# SCH_Keyboard_2024-07-21.net
KiCad netlist of a schematic drawn in EasyEDA
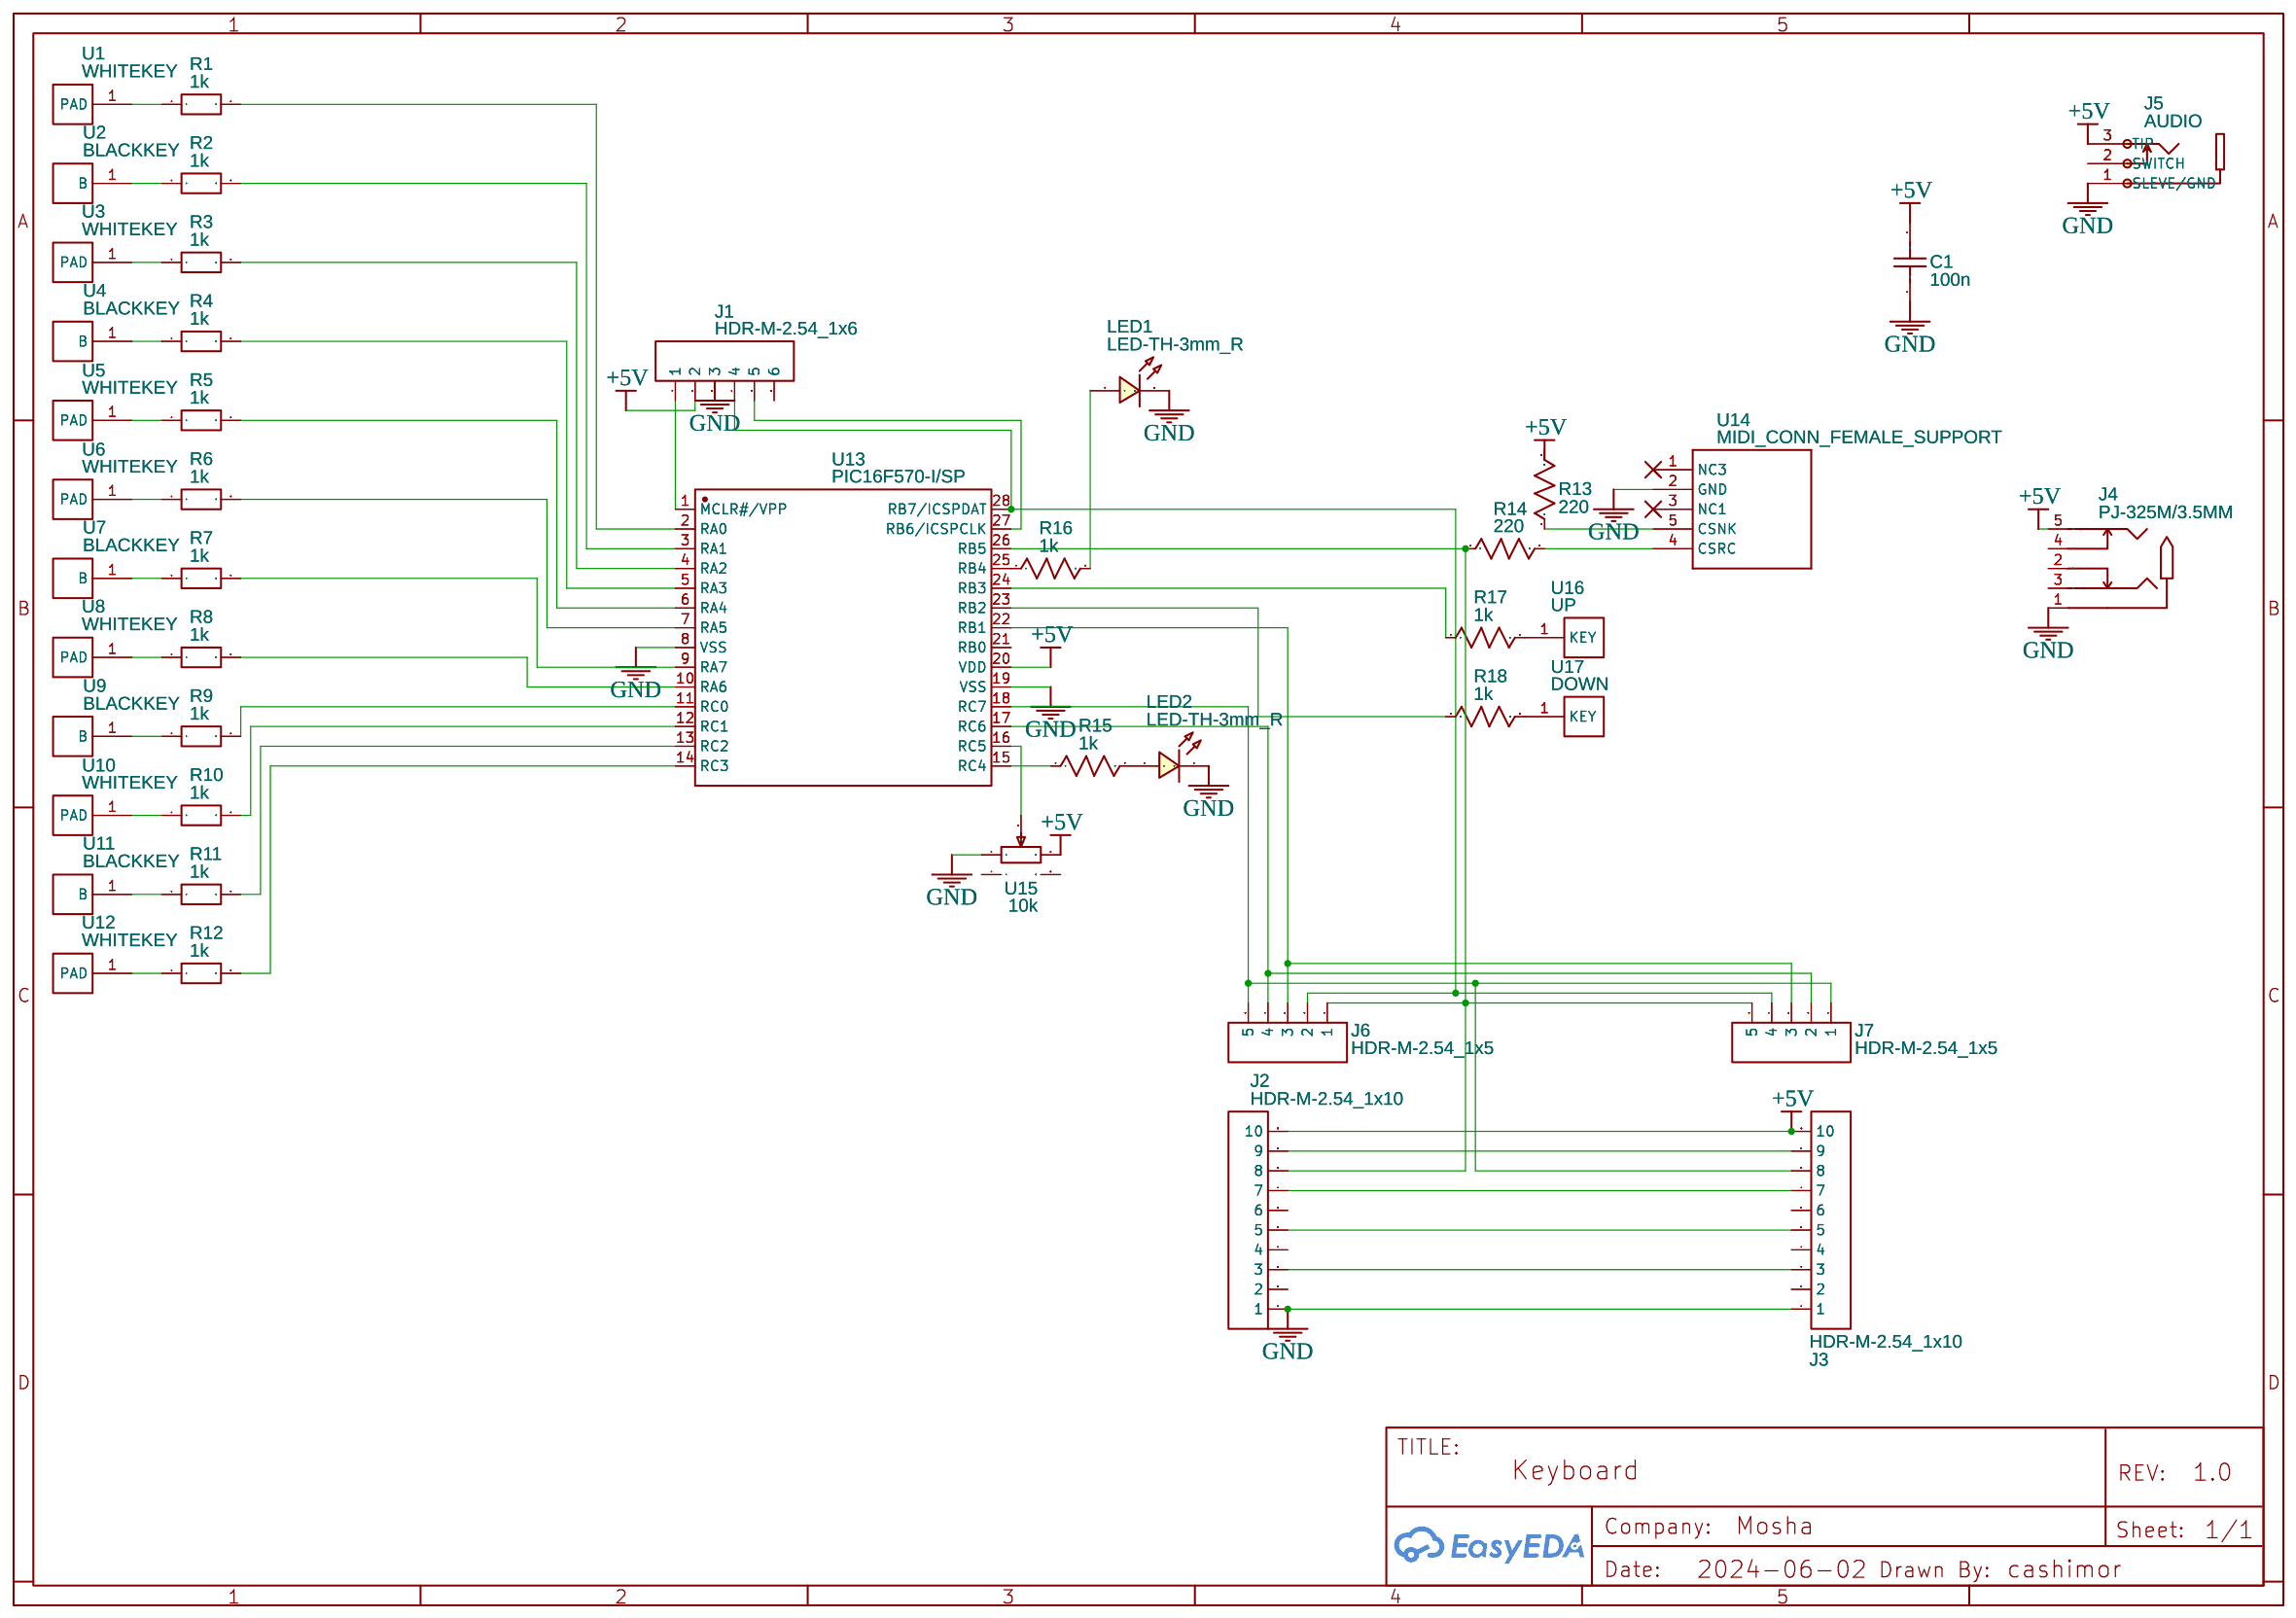
[diagram p0: schematic sheet]

(export (version "E")
  (design (tool "Eeschema 10.0.6"))
  (components
    (comp (ref "C1") (value "100n") (libsource (lib "") (part "C_RAD-0.1_US")))
    (comp (ref "J1") (value "HDR-M-2.54_1x6") (libsource (lib "") (part "HDR-M-2.54_1x6")))
    (comp (ref "J2") (value "HDR-M-2.54_1x10") (libsource (lib "") (part "HDR-M-2.54_1x10")))
    (comp (ref "J3") (value "HDR-M-2.54_1x10") (libsource (lib "") (part "HDR-M-2.54_1x10_1")))
    (comp (ref "J4")
      (value "PJ-325M/3.5MM")
      (fields (field (name "Manufacturer Part") "PJ325外铜套") (field (name "Manufacturer") "BOOMELE(博穆精密)"))
      (libsource (lib "") (part "PJ-325M/3.5MM"))
    )
    (comp (ref "J5")
      (value "AUDIO")
      (fields (field (name "Manufacturer Part") "Thonk"))
      (libsource (lib "") (part "THONKICONN_1"))
    )
    (comp (ref "J6") (value "HDR-M-2.54_1x5") (libsource (lib "") (part "HDR-M-2.54_1x5")))
    (comp (ref "J7") (value "HDR-M-2.54_1x5") (libsource (lib "") (part "HDR-M-2.54_1x5")))
    (comp (ref "LED1")
      (value "LED-TH-3mm_R")
      (fields
        (field (name "Manufacturer Part") "204-10SDRD/S530-A3-L")
        (field (name "Manufacturer") "EVERLIGHT(台湾亿光)")
      )
      (libsource (lib "") (part "LED-TH-3mm_R"))
    )
    (comp (ref "LED2")
      (value "LED-TH-3mm_R")
      (fields
        (field (name "Manufacturer Part") "204-10SDRD/S530-A3-L")
        (field (name "Manufacturer") "EVERLIGHT(台湾亿光)")
      )
      (libsource (lib "") (part "LED-TH-3mm_R"))
    )
    (comp (ref "R1") (value "1k") (libsource (lib "") (part "R_AXIAL-0.3_EU")))
    (comp (ref "R2") (value "1k") (libsource (lib "") (part "R_AXIAL-0.3_EU")))
    (comp (ref "R3") (value "1k") (libsource (lib "") (part "R_AXIAL-0.3_EU")))
    (comp (ref "R4") (value "1k") (libsource (lib "") (part "R_AXIAL-0.3_EU")))
    (comp (ref "R5") (value "1k") (libsource (lib "") (part "R_AXIAL-0.3_EU")))
    (comp (ref "R6") (value "1k") (libsource (lib "") (part "R_AXIAL-0.3_EU")))
    (comp (ref "R7") (value "1k") (libsource (lib "") (part "R_AXIAL-0.3_EU")))
    (comp (ref "R8") (value "1k") (libsource (lib "") (part "R_AXIAL-0.3_EU")))
    (comp (ref "R9") (value "1k") (libsource (lib "") (part "R_AXIAL-0.3_EU")))
    (comp (ref "R10") (value "1k") (libsource (lib "") (part "R_AXIAL-0.3_EU")))
    (comp (ref "R11") (value "1k") (libsource (lib "") (part "R_AXIAL-0.3_EU")))
    (comp (ref "R12") (value "1k") (libsource (lib "") (part "R_AXIAL-0.3_EU")))
    (comp (ref "R13") (value "220") (libsource (lib "") (part "R_AXIAL-0.3_US_1")))
    (comp (ref "R14") (value "220") (libsource (lib "") (part "R_AXIAL-0.3_US")))
    (comp (ref "R15") (value "1k") (libsource (lib "") (part "R_AXIAL-0.3_US")))
    (comp (ref "R16") (value "1k") (libsource (lib "") (part "R_AXIAL-0.3_US")))
    (comp (ref "R17") (value "1k") (libsource (lib "") (part "R_AXIAL-0.3_US")))
    (comp (ref "R18") (value "1k") (libsource (lib "") (part "R_AXIAL-0.3_US")))
    (comp (ref "U1") (value "WHITEKEY") (libsource (lib "") (part "WHITEKEY")))
    (comp (ref "U2") (value "BLACKKEY") (libsource (lib "") (part "BLACKKEY")))
    (comp (ref "U3") (value "WHITEKEY") (libsource (lib "") (part "WHITEKEY")))
    (comp (ref "U4") (value "BLACKKEY") (libsource (lib "") (part "BLACKKEY")))
    (comp (ref "U5") (value "WHITEKEY") (libsource (lib "") (part "WHITEKEY")))
    (comp (ref "U6") (value "WHITEKEY") (libsource (lib "") (part "WHITEKEY")))
    (comp (ref "U7") (value "BLACKKEY") (libsource (lib "") (part "BLACKKEY")))
    (comp (ref "U8") (value "WHITEKEY") (libsource (lib "") (part "WHITEKEY")))
    (comp (ref "U9") (value "BLACKKEY") (libsource (lib "") (part "BLACKKEY")))
    (comp (ref "U10") (value "WHITEKEY") (libsource (lib "") (part "WHITEKEY")))
    (comp (ref "U11") (value "BLACKKEY") (libsource (lib "") (part "BLACKKEY")))
    (comp (ref "U12") (value "WHITEKEY") (libsource (lib "") (part "WHITEKEY")))
    (comp (ref "U13")
      (value "PIC16F570-I/SP")
      (fields (field (name "Manufacturer") "MICROCHIP(美国微芯)"))
      (libsource (lib "") (part "PIC16F570-I/SP"))
    )
    (comp (ref "U14")
      (value "MIDI_CONN_FEMALE_SUPPORT")
      (libsource (lib "") (part "MIDI_CONN_FEMALE_SUPPORT"))
    )
    (comp (ref "U15")
      (value "10k")
      (fields (field (name "Manufacturer Part") "POT-R09V-100K"))
      (libsource (lib "") (part "POT-R09V-100K"))
    )
    (comp (ref "U16") (value "UP") (libsource (lib "") (part "PIANOTOUCHKEY")))
    (comp (ref "U17") (value "DOWN") (libsource (lib "") (part "PIANOTOUCHKEY")))
  )
  (nets
    (net (code "1") (name "+5V") (class "Default")
      (node (ref "C1") (pin "2") (pinfunction "2_2") (pintype "unspecified"))
      (node (ref "J1") (pin "2") (pinfunction "2_2") (pintype "input"))
      (node (ref "J2") (pin "10") (pinfunction "10_10") (pintype "unspecified"))
      (node (ref "J3") (pin "10") (pinfunction "10_10") (pintype "unspecified"))
      (node (ref "J4") (pin "5") (pinfunction "5_5") (pintype "input"))
      (node (ref "J5") (pin "3") (pinfunction "TIP_3") (pintype "unspecified"))
      (node (ref "R13") (pin "2") (pinfunction "2_2") (pintype "unspecified"))
      (node (ref "U13") (pin "20") (pinfunction "VDD_20") (pintype "unspecified"))
      (node (ref "U15") (pin "3") (pinfunction "3_3") (pintype "input"))
    )
    (net (code "2") (name "GND") (class "Default")
      (node (ref "C1") (pin "1") (pinfunction "1_1") (pintype "unspecified"))
      (node (ref "J1") (pin "3") (pinfunction "3_3") (pintype "input"))
      (node (ref "J2") (pin "1") (pinfunction "1_1") (pintype "unspecified"))
      (node (ref "J3") (pin "1") (pinfunction "1_1") (pintype "unspecified"))
      (node (ref "J4") (pin "1") (pinfunction "1_1") (pintype "input"))
      (node (ref "J5") (pin "1") (pinfunction "SLEVE/GND_1") (pintype "unspecified"))
      (node (ref "LED1") (pin "2") (pinfunction "2_2") (pintype "unspecified"))
      (node (ref "LED2") (pin "2") (pinfunction "2_2") (pintype "unspecified"))
      (node (ref "U13") (pin "19") (pinfunction "VSS_19") (pintype "unspecified"))
      (node (ref "U13") (pin "8") (pinfunction "VSS_8") (pintype "unspecified"))
      (node (ref "U14") (pin "2") (pinfunction "GND_2") (pintype "unspecified"))
      (node (ref "U15") (pin "1") (pinfunction "1_1") (pintype "input"))
    )
    (net (code "3") (name "Net-(J2-Pad3)") (class "Default")
      (node (ref "J2") (pin "3") (pinfunction "3_3") (pintype "unspecified"))
      (node (ref "J3") (pin "3") (pinfunction "3_3") (pintype "unspecified"))
    )
    (net (code "4") (name "Net-(J2-Pad5)") (class "Default")
      (node (ref "J2") (pin "5") (pinfunction "5_5") (pintype "unspecified"))
      (node (ref "J3") (pin "5") (pinfunction "5_5") (pintype "unspecified"))
    )
    (net (code "5") (name "Net-(J2-Pad7)") (class "Default")
      (node (ref "J2") (pin "7") (pinfunction "7_7") (pintype "unspecified"))
      (node (ref "J3") (pin "7") (pinfunction "7_7") (pintype "unspecified"))
    )
    (net (code "6") (name "Net-(J2-Pad9)") (class "Default")
      (node (ref "J2") (pin "9") (pinfunction "9_9") (pintype "unspecified"))
      (node (ref "J3") (pin "9") (pinfunction "9_9") (pintype "unspecified"))
    )
    (net (code "7") (name "Net-(LED1-Pad1)") (class "Default")
      (node (ref "LED1") (pin "1") (pinfunction "1_1") (pintype "unspecified"))
      (node (ref "R16") (pin "2") (pinfunction "2_2") (pintype "unspecified"))
    )
    (net (code "8") (name "Net-(LED2-Pad1)") (class "Default")
      (node (ref "LED2") (pin "1") (pinfunction "1_1") (pintype "unspecified"))
      (node (ref "R15") (pin "2") (pinfunction "2_2") (pintype "unspecified"))
    )
    (net (code "9") (name "Net-(U1-PAD)") (class "Default")
      (node (ref "R1") (pin "1") (pinfunction "1_1") (pintype "unspecified"))
      (node (ref "U1") (pin "1") (pinfunction "PAD_1") (pintype "unspecified"))
    )
    (net (code "10") (name "Net-(U2-B)") (class "Default")
      (node (ref "R2") (pin "1") (pinfunction "1_1") (pintype "unspecified"))
      (node (ref "U2") (pin "1") (pinfunction "B_1") (pintype "unspecified"))
    )
    (net (code "11") (name "Net-(U3-PAD)") (class "Default")
      (node (ref "R3") (pin "1") (pinfunction "1_1") (pintype "unspecified"))
      (node (ref "U3") (pin "1") (pinfunction "PAD_1") (pintype "unspecified"))
    )
    (net (code "12") (name "Net-(U4-B)") (class "Default")
      (node (ref "R4") (pin "1") (pinfunction "1_1") (pintype "unspecified"))
      (node (ref "U4") (pin "1") (pinfunction "B_1") (pintype "unspecified"))
    )
    (net (code "13") (name "Net-(U5-PAD)") (class "Default")
      (node (ref "R5") (pin "1") (pinfunction "1_1") (pintype "unspecified"))
      (node (ref "U5") (pin "1") (pinfunction "PAD_1") (pintype "unspecified"))
    )
    (net (code "14") (name "Net-(U6-PAD)") (class "Default")
      (node (ref "R6") (pin "1") (pinfunction "1_1") (pintype "unspecified"))
      (node (ref "U6") (pin "1") (pinfunction "PAD_1") (pintype "unspecified"))
    )
    (net (code "15") (name "Net-(U7-B)") (class "Default")
      (node (ref "R7") (pin "1") (pinfunction "1_1") (pintype "unspecified"))
      (node (ref "U7") (pin "1") (pinfunction "B_1") (pintype "unspecified"))
    )
    (net (code "16") (name "Net-(U8-PAD)") (class "Default")
      (node (ref "R8") (pin "1") (pinfunction "1_1") (pintype "unspecified"))
      (node (ref "U8") (pin "1") (pinfunction "PAD_1") (pintype "unspecified"))
    )
    (net (code "17") (name "Net-(U9-B)") (class "Default")
      (node (ref "R9") (pin "1") (pinfunction "1_1") (pintype "unspecified"))
      (node (ref "U9") (pin "1") (pinfunction "B_1") (pintype "unspecified"))
    )
    (net (code "18") (name "Net-(U10-PAD)") (class "Default")
      (node (ref "R10") (pin "1") (pinfunction "1_1") (pintype "unspecified"))
      (node (ref "U10") (pin "1") (pinfunction "PAD_1") (pintype "unspecified"))
    )
    (net (code "19") (name "Net-(U11-B)") (class "Default")
      (node (ref "R11") (pin "1") (pinfunction "1_1") (pintype "unspecified"))
      (node (ref "U11") (pin "1") (pinfunction "B_1") (pintype "unspecified"))
    )
    (net (code "20") (name "Net-(U12-PAD)") (class "Default")
      (node (ref "R12") (pin "1") (pinfunction "1_1") (pintype "unspecified"))
      (node (ref "U12") (pin "1") (pinfunction "PAD_1") (pintype "unspecified"))
    )
    (net (code "21") (name "Net-(U13-MCLR#{slash}VPP)") (class "Default")
      (node (ref "J1") (pin "1") (pinfunction "1_1") (pintype "input"))
      (node (ref "U13") (pin "1") (pinfunction "MCLR#/VPP_1") (pintype "unspecified"))
    )
    (net (code "22") (name "Net-(U13-RA0)") (class "Default")
      (node (ref "R1") (pin "2") (pinfunction "2_2") (pintype "unspecified"))
      (node (ref "U13") (pin "2") (pinfunction "RA0_2") (pintype "unspecified"))
    )
    (net (code "23") (name "Net-(U13-RA1)") (class "Default")
      (node (ref "R2") (pin "2") (pinfunction "2_2") (pintype "unspecified"))
      (node (ref "U13") (pin "3") (pinfunction "RA1_3") (pintype "unspecified"))
    )
    (net (code "24") (name "Net-(U13-RA2)") (class "Default")
      (node (ref "R3") (pin "2") (pinfunction "2_2") (pintype "unspecified"))
      (node (ref "U13") (pin "4") (pinfunction "RA2_4") (pintype "unspecified"))
    )
    (net (code "25") (name "Net-(U13-RA3)") (class "Default")
      (node (ref "R4") (pin "2") (pinfunction "2_2") (pintype "unspecified"))
      (node (ref "U13") (pin "5") (pinfunction "RA3_5") (pintype "unspecified"))
    )
    (net (code "26") (name "Net-(U13-RA4)") (class "Default")
      (node (ref "R5") (pin "2") (pinfunction "2_2") (pintype "unspecified"))
      (node (ref "U13") (pin "6") (pinfunction "RA4_6") (pintype "unspecified"))
    )
    (net (code "27") (name "Net-(U13-RA5)") (class "Default")
      (node (ref "R6") (pin "2") (pinfunction "2_2") (pintype "unspecified"))
      (node (ref "U13") (pin "7") (pinfunction "RA5_7") (pintype "unspecified"))
    )
    (net (code "28") (name "Net-(U13-RA6)") (class "Default")
      (node (ref "R8") (pin "2") (pinfunction "2_2") (pintype "unspecified"))
      (node (ref "U13") (pin "10") (pinfunction "RA6_10") (pintype "unspecified"))
    )
    (net (code "29") (name "Net-(U13-RA7)") (class "Default")
      (node (ref "R7") (pin "2") (pinfunction "2_2") (pintype "unspecified"))
      (node (ref "U13") (pin "9") (pinfunction "RA7_9") (pintype "unspecified"))
    )
    (net (code "30") (name "Net-(U13-RB1)") (class "Default")
      (node (ref "J6") (pin "3") (pinfunction "3_3") (pintype "unspecified"))
      (node (ref "J7") (pin "3") (pinfunction "3_3") (pintype "unspecified"))
      (node (ref "U13") (pin "22") (pinfunction "RB1_22") (pintype "unspecified"))
    )
    (net (code "31") (name "Net-(U13-RB2)") (class "Default")
      (node (ref "R18") (pin "1") (pinfunction "1_1") (pintype "unspecified"))
      (node (ref "U13") (pin "23") (pinfunction "RB2_23") (pintype "unspecified"))
    )
    (net (code "32") (name "Net-(U13-RB3)") (class "Default")
      (node (ref "R17") (pin "1") (pinfunction "1_1") (pintype "unspecified"))
      (node (ref "U13") (pin "24") (pinfunction "RB3_24") (pintype "unspecified"))
    )
    (net (code "33") (name "Net-(U13-RB4)") (class "Default")
      (node (ref "R16") (pin "1") (pinfunction "1_1") (pintype "unspecified"))
      (node (ref "U13") (pin "25") (pinfunction "RB4_25") (pintype "unspecified"))
    )
    (net (code "34") (name "Net-(U13-RB5)") (class "Default")
      (node (ref "J2") (pin "8") (pinfunction "8_8") (pintype "unspecified"))
      (node (ref "J6") (pin "1") (pinfunction "1_1") (pintype "unspecified"))
      (node (ref "J7") (pin "5") (pinfunction "5_5") (pintype "unspecified"))
      (node (ref "R14") (pin "1") (pinfunction "1_1") (pintype "unspecified"))
      (node (ref "U13") (pin "26") (pinfunction "RB5_26") (pintype "unspecified"))
    )
    (net (code "35") (name "Net-(U13-RB6{slash}ICSPCLK)") (class "Default")
      (node (ref "J1") (pin "5") (pinfunction "5_5") (pintype "input"))
      (node (ref "U13") (pin "27") (pinfunction "RB6/ICSPCLK_27") (pintype "unspecified"))
    )
    (net (code "36") (name "Net-(U13-RB7{slash}ICSPDAT)") (class "Default")
      (node (ref "J1") (pin "4") (pinfunction "4_4") (pintype "input"))
      (node (ref "J6") (pin "2") (pinfunction "2_2") (pintype "unspecified"))
      (node (ref "J7") (pin "4") (pinfunction "4_4") (pintype "unspecified"))
      (node (ref "U13") (pin "28") (pinfunction "RB7/ICSPDAT_28") (pintype "unspecified"))
    )
    (net (code "37") (name "Net-(U13-RC0)") (class "Default")
      (node (ref "R9") (pin "2") (pinfunction "2_2") (pintype "unspecified"))
      (node (ref "U13") (pin "11") (pinfunction "RC0_11") (pintype "unspecified"))
    )
    (net (code "38") (name "Net-(U13-RC1)") (class "Default")
      (node (ref "R10") (pin "2") (pinfunction "2_2") (pintype "unspecified"))
      (node (ref "U13") (pin "12") (pinfunction "RC1_12") (pintype "unspecified"))
    )
    (net (code "39") (name "Net-(U13-RC2)") (class "Default")
      (node (ref "R11") (pin "2") (pinfunction "2_2") (pintype "unspecified"))
      (node (ref "U13") (pin "13") (pinfunction "RC2_13") (pintype "unspecified"))
    )
    (net (code "40") (name "Net-(U13-RC3)") (class "Default")
      (node (ref "R12") (pin "2") (pinfunction "2_2") (pintype "unspecified"))
      (node (ref "U13") (pin "14") (pinfunction "RC3_14") (pintype "unspecified"))
    )
    (net (code "41") (name "Net-(U13-RC4)") (class "Default")
      (node (ref "R15") (pin "1") (pinfunction "1_1") (pintype "unspecified"))
      (node (ref "U13") (pin "15") (pinfunction "RC4_15") (pintype "unspecified"))
    )
    (net (code "42") (name "Net-(U13-RC5)") (class "Default")
      (node (ref "U13") (pin "16") (pinfunction "RC5_16") (pintype "unspecified"))
      (node (ref "U15") (pin "2") (pinfunction "2_2") (pintype "input"))
    )
    (net (code "43") (name "Net-(U13-RC6)") (class "Default")
      (node (ref "J6") (pin "4") (pinfunction "4_4") (pintype "unspecified"))
      (node (ref "J7") (pin "2") (pinfunction "2_2") (pintype "unspecified"))
      (node (ref "U13") (pin "17") (pinfunction "RC6_17") (pintype "unspecified"))
    )
    (net (code "44") (name "Net-(U13-RC7)") (class "Default")
      (node (ref "J3") (pin "8") (pinfunction "8_8") (pintype "unspecified"))
      (node (ref "J6") (pin "5") (pinfunction "5_5") (pintype "unspecified"))
      (node (ref "J7") (pin "1") (pinfunction "1_1") (pintype "unspecified"))
      (node (ref "U13") (pin "18") (pinfunction "RC7_18") (pintype "unspecified"))
    )
    (net (code "45") (name "Net-(U14-CSNK)") (class "Default")
      (node (ref "R13") (pin "1") (pinfunction "1_1") (pintype "unspecified"))
      (node (ref "U14") (pin "5") (pinfunction "CSNK_5") (pintype "unspecified"))
    )
    (net (code "46") (name "Net-(U14-CSRC)") (class "Default")
      (node (ref "R14") (pin "2") (pinfunction "2_2") (pintype "unspecified"))
      (node (ref "U14") (pin "4") (pinfunction "CSRC_4") (pintype "unspecified"))
    )
    (net (code "47") (name "Net-(U16-KEY)") (class "Default")
      (node (ref "R17") (pin "2") (pinfunction "2_2") (pintype "unspecified"))
      (node (ref "U16") (pin "1") (pinfunction "KEY_1") (pintype "unspecified"))
    )
    (net (code "48") (name "Net-(U17-KEY)") (class "Default")
      (node (ref "R18") (pin "2") (pinfunction "2_2") (pintype "unspecified"))
      (node (ref "U17") (pin "1") (pinfunction "KEY_1") (pintype "unspecified"))
    )
    (net (code "49") (name "unconnected-(J1-Pad6)") (class "Default")
      (node (ref "J1") (pin "6") (pinfunction "6_6") (pintype "input"))
    )
    (net (code "50") (name "unconnected-(J2-Pad2)") (class "Default")
      (node (ref "J2") (pin "2") (pinfunction "2_2") (pintype "unspecified"))
    )
    (net (code "51") (name "unconnected-(J2-Pad4)") (class "Default")
      (node (ref "J2") (pin "4") (pinfunction "4_4") (pintype "unspecified"))
    )
    (net (code "52") (name "unconnected-(J2-Pad6)") (class "Default")
      (node (ref "J2") (pin "6") (pinfunction "6_6") (pintype "unspecified"))
    )
    (net (code "53") (name "unconnected-(J3-Pad2)") (class "Default")
      (node (ref "J3") (pin "2") (pinfunction "2_2") (pintype "unspecified"))
    )
    (net (code "54") (name "unconnected-(J3-Pad4)") (class "Default")
      (node (ref "J3") (pin "4") (pinfunction "4_4") (pintype "unspecified"))
    )
    (net (code "55") (name "unconnected-(J3-Pad6)") (class "Default")
      (node (ref "J3") (pin "6") (pinfunction "6_6") (pintype "unspecified"))
    )
    (net (code "56") (name "unconnected-(J4-Pad2)") (class "Default")
      (node (ref "J4") (pin "2") (pinfunction "2_2") (pintype "input"))
    )
    (net (code "57") (name "unconnected-(J4-Pad3)") (class "Default")
      (node (ref "J4") (pin "3") (pinfunction "3_3") (pintype "input"))
    )
    (net (code "58") (name "unconnected-(J4-Pad4)") (class "Default")
      (node (ref "J4") (pin "4") (pinfunction "4_4") (pintype "input"))
    )
    (net (code "59") (name "unconnected-(J5-SWITCH-Pad2)") (class "Default")
      (node (ref "J5") (pin "2") (pinfunction "SWITCH_2") (pintype "unspecified"))
    )
    (net (code "60") (name "unconnected-(U13-RB0-Pad21)") (class "Default")
      (node (ref "U13") (pin "21") (pinfunction "RB0_21") (pintype "unspecified"))
    )
    (net (code "61") (name "unconnected-(U14-NC1-Pad3)") (class "Default")
      (node (ref "U14") (pin "3") (pinfunction "NC1_3") (pintype "unspecified"))
    )
    (net (code "62") (name "unconnected-(U14-NC3-Pad1)") (class "Default")
      (node (ref "U14") (pin "1") (pinfunction "NC3_1") (pintype "unspecified"))
    )
    (net (code "63") (name "unconnected-(U15-Pad4)") (class "Default")
      (node (ref "U15") (pin "4") (pinfunction "4_4") (pintype "input"))
    )
    (net (code "64") (name "unconnected-(U15-Pad5)") (class "Default")
      (node (ref "U15") (pin "5") (pinfunction "5_5") (pintype "input"))
    )
  )
)
